# CircuitoClasificadorv1.net
KiCad netlist of a schematic drawn in EAGLE
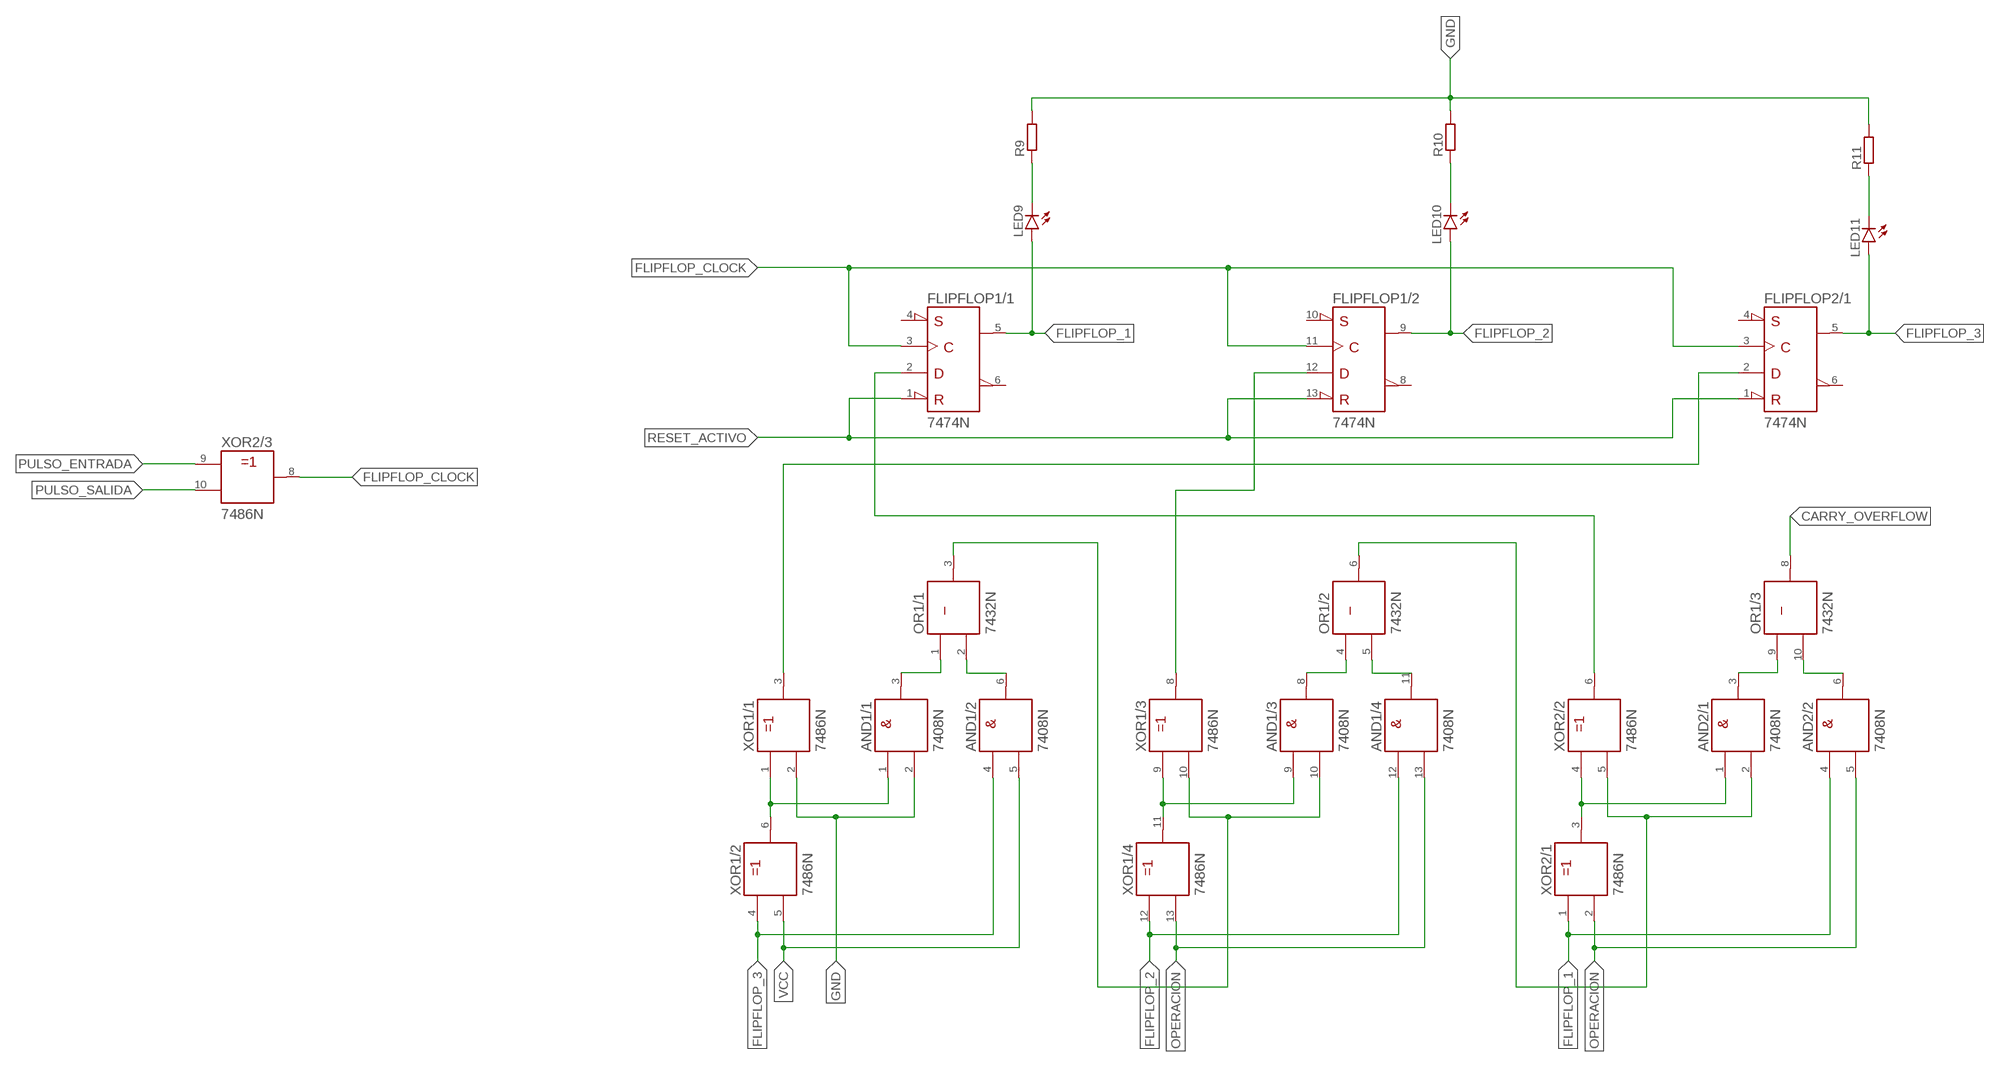
[diagram p0: schematic, sheet 1, part 1 of 2]
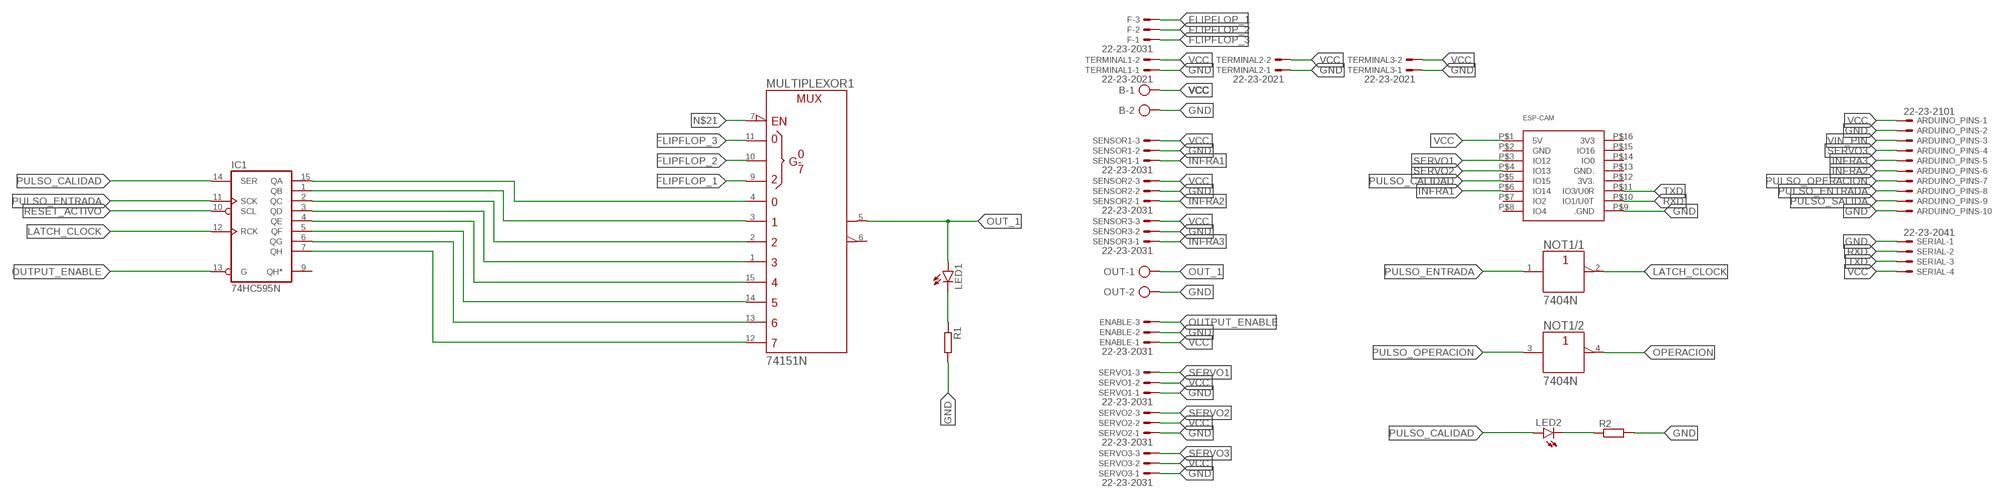
[diagram p1: schematic, sheet 1, part 2 of 2]

(export (version "E")
  (design (tool "Eeschema 10.0.6"))
  (components
    (comp (ref "AND1")
      (value "7408N")
      (footprint "eagle-import:DIL14")
      (libsource (lib "eagle-import") (part "7408N"))
    )
    (comp (ref "AND2")
      (value "7408N")
      (footprint "eagle-import:DIL14")
      (libsource (lib "eagle-import") (part "7408N"))
    )
    (comp (ref "ARDUINO_PINS")
      (value "22-23-2101")
      (footprint "eagle-import:22-23-2101")
      (fields (field (name "MF") "MOLEX"))
      (libsource (lib "eagle-import") (part "22-23-2101"))
    )
    (comp (ref "B")
      (value "AK500/2")
      (footprint "eagle-import:AK500_2")
      (libsource (lib "eagle-import") (part "AK500/2"))
    )
    (comp (ref "ENABLE")
      (value "22-23-2031")
      (footprint "eagle-import:22-23-2031")
      (fields (field (name "MF") "MOLEX"))
      (libsource (lib "eagle-import") (part "22-23-2031"))
    )
    (comp (ref "ESP-CAM")
      (value "ESP32-CAM")
      (footprint "eagle-import:ESP32-CAM")
      (fields (field (name "MF") "AI-Thinker"))
      (libsource (lib "eagle-import") (part "ESP32-CAM"))
    )
    (comp (ref "F")
      (value "22-23-2031")
      (footprint "eagle-import:22-23-2031")
      (fields (field (name "MF") "MOLEX"))
      (libsource (lib "eagle-import") (part "22-23-2031"))
    )
    (comp (ref "FLIPFLOP1")
      (value "7474N")
      (footprint "eagle-import:DIL14")
      (libsource (lib "eagle-import") (part "7474N"))
    )
    (comp (ref "FLIPFLOP2")
      (value "7474N")
      (footprint "eagle-import:DIL14")
      (libsource (lib "eagle-import") (part "7474N"))
    )
    (comp (ref "IC1")
      (value "74HC595N")
      (footprint "eagle-import:DIL16")
      (libsource (lib "eagle-import") (part "74595NHC"))
    )
    (comp (ref "LED1")
      (value "LED5MM")
      (footprint "eagle-import:LED5MM")
      (libsource (lib "eagle-import") (part "LED5MM"))
    )
    (comp (ref "LED2")
      (value "LED5MM")
      (footprint "eagle-import:LED5MM")
      (libsource (lib "eagle-import") (part "LED5MM"))
    )
    (comp (ref "LED9")
      (value "LED5MM")
      (footprint "eagle-import:LED5MM")
      (libsource (lib "eagle-import") (part "LED5MM"))
    )
    (comp (ref "LED10")
      (value "LED5MM")
      (footprint "eagle-import:LED5MM")
      (libsource (lib "eagle-import") (part "LED5MM"))
    )
    (comp (ref "LED11")
      (value "LED5MM")
      (footprint "eagle-import:LED5MM")
      (libsource (lib "eagle-import") (part "LED5MM"))
    )
    (comp (ref "MULTIPLEXOR1")
      (value "74151N")
      (footprint "eagle-import:DIL16")
      (libsource (lib "eagle-import") (part "74151N"))
    )
    (comp (ref "NOT1")
      (value "7404N")
      (footprint "eagle-import:DIL14")
      (libsource (lib "eagle-import") (part "7404N"))
    )
    (comp (ref "OR1")
      (value "7432N")
      (footprint "eagle-import:DIL14")
      (libsource (lib "eagle-import") (part "7432N"))
    )
    (comp (ref "OUT")
      (value "AK500/2-H")
      (footprint "eagle-import:AK500_2-H")
      (libsource (lib "eagle-import") (part "AK500/2-H"))
    )
    (comp (ref "R1")
      (value "R-EU_0207/10")
      (footprint "eagle-import:0207_10")
      (libsource (lib "eagle-import") (part "R-EU_0207/10"))
    )
    (comp (ref "R2")
      (value "R-EU_0207/10")
      (footprint "eagle-import:0207_10")
      (libsource (lib "eagle-import") (part "R-EU_0207/10"))
    )
    (comp (ref "R9")
      (value "R-EU_0207/10")
      (footprint "eagle-import:0207_10")
      (libsource (lib "eagle-import") (part "R-EU_0207/10"))
    )
    (comp (ref "R10")
      (value "R-EU_0207/10")
      (footprint "eagle-import:0207_10")
      (libsource (lib "eagle-import") (part "R-EU_0207/10"))
    )
    (comp (ref "R11")
      (value "R-EU_0207/10")
      (footprint "eagle-import:0207_10")
      (libsource (lib "eagle-import") (part "R-EU_0207/10"))
    )
    (comp (ref "SENSOR1")
      (value "22-23-2031")
      (footprint "eagle-import:22-23-2031")
      (fields (field (name "MF") "MOLEX"))
      (libsource (lib "eagle-import") (part "22-23-2031"))
    )
    (comp (ref "SENSOR2")
      (value "22-23-2031")
      (footprint "eagle-import:22-23-2031")
      (fields (field (name "MF") "MOLEX"))
      (libsource (lib "eagle-import") (part "22-23-2031"))
    )
    (comp (ref "SENSOR3")
      (value "22-23-2031")
      (footprint "eagle-import:22-23-2031")
      (fields (field (name "MF") "MOLEX"))
      (libsource (lib "eagle-import") (part "22-23-2031"))
    )
    (comp (ref "SERIAL")
      (value "22-23-2041")
      (footprint "eagle-import:22-23-2041")
      (fields (field (name "MF") "MOLEX"))
      (libsource (lib "eagle-import") (part "22-23-2041"))
    )
    (comp (ref "SERVO1")
      (value "22-23-2031")
      (footprint "eagle-import:22-23-2031")
      (fields (field (name "MF") "MOLEX"))
      (libsource (lib "eagle-import") (part "22-23-2031"))
    )
    (comp (ref "SERVO2")
      (value "22-23-2031")
      (footprint "eagle-import:22-23-2031")
      (fields (field (name "MF") "MOLEX"))
      (libsource (lib "eagle-import") (part "22-23-2031"))
    )
    (comp (ref "SERVO3")
      (value "22-23-2031")
      (footprint "eagle-import:22-23-2031")
      (fields (field (name "MF") "MOLEX"))
      (libsource (lib "eagle-import") (part "22-23-2031"))
    )
    (comp (ref "TERMINAL1")
      (value "22-23-2021")
      (footprint "eagle-import:22-23-2021")
      (fields (field (name "MF") "MOLEX"))
      (libsource (lib "eagle-import") (part "22-23-2021"))
    )
    (comp (ref "TERMINAL2")
      (value "22-23-2021")
      (footprint "eagle-import:22-23-2021")
      (fields (field (name "MF") "MOLEX"))
      (libsource (lib "eagle-import") (part "22-23-2021"))
    )
    (comp (ref "TERMINAL3")
      (value "22-23-2021")
      (footprint "eagle-import:22-23-2021")
      (fields (field (name "MF") "MOLEX"))
      (libsource (lib "eagle-import") (part "22-23-2021"))
    )
    (comp (ref "XOR1")
      (value "7486N")
      (footprint "eagle-import:DIL14")
      (libsource (lib "eagle-import") (part "7486N"))
    )
    (comp (ref "XOR2")
      (value "7486N")
      (footprint "eagle-import:DIL14")
      (libsource (lib "eagle-import") (part "7486N"))
    )
  )
  (nets
    (net (code "1") (name "CARRY_OVERFLOW") (class "Default")
      (node (ref "OR1") (pin "8") (pinfunction "Y_8") (pintype "output"))
    )
    (net (code "2") (name "FLIPFLOP_1") (class "Default")
      (node (ref "AND2") (pin "4") (pinfunction "A_4") (pintype "input"))
      (node (ref "F") (pin "3") (pinfunction "S_3") (pintype "passive"))
      (node (ref "FLIPFLOP1") (pin "5") (pinfunction "Q_5") (pintype "output"))
      (node (ref "LED9") (pin "A") (pinfunction "A_A") (pintype "passive"))
      (node (ref "MULTIPLEXOR1") (pin "9") (pinfunction "C_9") (pintype "input"))
      (node (ref "XOR2") (pin "1") (pinfunction "A_1") (pintype "input"))
    )
    (net (code "3") (name "FLIPFLOP_2") (class "Default")
      (node (ref "AND1") (pin "12") (pinfunction "A_12") (pintype "input"))
      (node (ref "F") (pin "2") (pinfunction "S_2") (pintype "passive"))
      (node (ref "FLIPFLOP1") (pin "9") (pinfunction "Q_9") (pintype "output"))
      (node (ref "LED10") (pin "A") (pinfunction "A_A") (pintype "passive"))
      (node (ref "MULTIPLEXOR1") (pin "10") (pinfunction "B_10") (pintype "input"))
      (node (ref "XOR1") (pin "12") (pinfunction "A_12") (pintype "input"))
    )
    (net (code "4") (name "FLIPFLOP_3") (class "Default")
      (node (ref "AND1") (pin "4") (pinfunction "A_4") (pintype "input"))
      (node (ref "F") (pin "1") (pinfunction "S_1") (pintype "passive"))
      (node (ref "FLIPFLOP2") (pin "5") (pinfunction "Q_5") (pintype "output"))
      (node (ref "LED11") (pin "A") (pinfunction "A_A") (pintype "passive"))
      (node (ref "MULTIPLEXOR1") (pin "11") (pinfunction "A_11") (pintype "input"))
      (node (ref "XOR1") (pin "4") (pinfunction "A_4") (pintype "input"))
    )
    (net (code "5") (name "FLIPFLOP_CLOCK") (class "Default")
      (node (ref "FLIPFLOP1") (pin "11") (pinfunction "CLK_11") (pintype "input"))
      (node (ref "FLIPFLOP1") (pin "3") (pinfunction "CLK_3") (pintype "input"))
      (node (ref "FLIPFLOP2") (pin "3") (pinfunction "CLK_3") (pintype "input"))
      (node (ref "XOR2") (pin "8") (pinfunction "Y_8") (pintype "output"))
    )
    (net (code "6") (name "GND") (class "Default")
      (node (ref "AND1") (pin "2") (pinfunction "B_2") (pintype "input"))
      (node (ref "ARDUINO_PINS") (pin "10") (pinfunction "S_10") (pintype "passive"))
      (node (ref "ARDUINO_PINS") (pin "2") (pinfunction "S_2") (pintype "passive"))
      (node (ref "B") (pin "2") (pinfunction "KL_2") (pintype "passive"))
      (node (ref "ENABLE") (pin "2") (pinfunction "S_2") (pintype "passive"))
      (node (ref "ESP-CAM") (pin "P$9") (pinfunction ".GND_P$9") (pintype "bidirectional"))
      (node (ref "OUT") (pin "2") (pinfunction "KL_2") (pintype "passive"))
      (node (ref "R1") (pin "2") (pinfunction "2_2") (pintype "passive"))
      (node (ref "R10") (pin "2") (pinfunction "2_2") (pintype "passive"))
      (node (ref "R11") (pin "2") (pinfunction "2_2") (pintype "passive"))
      (node (ref "R2") (pin "2") (pinfunction "2_2") (pintype "passive"))
      (node (ref "R9") (pin "2") (pinfunction "2_2") (pintype "passive"))
      (node (ref "SENSOR1") (pin "2") (pinfunction "S_2") (pintype "passive"))
      (node (ref "SENSOR2") (pin "2") (pinfunction "S_2") (pintype "passive"))
      (node (ref "SENSOR3") (pin "2") (pinfunction "S_2") (pintype "passive"))
      (node (ref "SERIAL") (pin "1") (pinfunction "S_1") (pintype "passive"))
      (node (ref "SERVO1") (pin "1") (pinfunction "S_1") (pintype "passive"))
      (node (ref "SERVO2") (pin "1") (pinfunction "S_1") (pintype "passive"))
      (node (ref "SERVO3") (pin "1") (pinfunction "S_1") (pintype "passive"))
      (node (ref "TERMINAL1") (pin "1") (pinfunction "S_1") (pintype "passive"))
      (node (ref "TERMINAL2") (pin "1") (pinfunction "S_1") (pintype "passive"))
      (node (ref "TERMINAL3") (pin "1") (pinfunction "S_1") (pintype "passive"))
      (node (ref "XOR1") (pin "2") (pinfunction "B_2") (pintype "input"))
    )
    (net (code "7") (name "INFRA1") (class "Default")
      (node (ref "ESP-CAM") (pin "P$6") (pinfunction "IO14_P$6") (pintype "bidirectional"))
      (node (ref "SENSOR1") (pin "1") (pinfunction "S_1") (pintype "passive"))
    )
    (net (code "8") (name "INFRA2") (class "Default")
      (node (ref "ARDUINO_PINS") (pin "6") (pinfunction "S_6") (pintype "passive"))
      (node (ref "SENSOR2") (pin "1") (pinfunction "S_1") (pintype "passive"))
    )
    (net (code "9") (name "INFRA3") (class "Default")
      (node (ref "ARDUINO_PINS") (pin "5") (pinfunction "S_5") (pintype "passive"))
      (node (ref "SENSOR3") (pin "1") (pinfunction "S_1") (pintype "passive"))
    )
    (net (code "10") (name "LATCH_CLOCK") (class "Default")
      (node (ref "IC1") (pin "12") (pinfunction "RCK_12") (pintype "input"))
      (node (ref "NOT1") (pin "2") (pinfunction "Y_2") (pintype "output"))
    )
    (net (code "11") (name "N$21") (class "Default")
      (node (ref "MULTIPLEXOR1") (pin "7") (pinfunction "~{G}_7") (pintype "input"))
    )
    (net (code "12") (name "Net-(AND1C-A)") (class "Default")
      (node (ref "AND1") (pin "1") (pinfunction "A_1") (pintype "input"))
      (node (ref "XOR1") (pin "1") (pinfunction "A_1") (pintype "input"))
      (node (ref "XOR1") (pin "6") (pinfunction "Y_6") (pintype "output"))
    )
    (net (code "13") (name "Net-(AND1C-Y)") (class "Default")
      (node (ref "AND1") (pin "3") (pinfunction "Y_3") (pintype "output"))
      (node (ref "OR1") (pin "1") (pinfunction "A_1") (pintype "input"))
    )
    (net (code "14") (name "Net-(AND1D-Y)") (class "Default")
      (node (ref "AND1") (pin "6") (pinfunction "Y_6") (pintype "output"))
      (node (ref "OR1") (pin "2") (pinfunction "B_2") (pintype "input"))
    )
    (net (code "15") (name "Net-(AND1E-A)") (class "Default")
      (node (ref "AND1") (pin "9") (pinfunction "A_9") (pintype "input"))
      (node (ref "XOR1") (pin "11") (pinfunction "Y_11") (pintype "output"))
      (node (ref "XOR1") (pin "9") (pinfunction "A_9") (pintype "input"))
    )
    (net (code "16") (name "Net-(AND1E-B)") (class "Default")
      (node (ref "AND1") (pin "10") (pinfunction "B_10") (pintype "input"))
      (node (ref "OR1") (pin "3") (pinfunction "Y_3") (pintype "output"))
      (node (ref "XOR1") (pin "10") (pinfunction "B_10") (pintype "input"))
    )
    (net (code "17") (name "Net-(AND1E-Y)") (class "Default")
      (node (ref "AND1") (pin "8") (pinfunction "Y_8") (pintype "output"))
      (node (ref "OR1") (pin "4") (pinfunction "A_4") (pintype "input"))
    )
    (net (code "18") (name "Net-(AND1F-Y)") (class "Default")
      (node (ref "AND1") (pin "11") (pinfunction "Y_11") (pintype "output"))
      (node (ref "OR1") (pin "5") (pinfunction "B_5") (pintype "input"))
    )
    (net (code "19") (name "Net-(AND2C-A)") (class "Default")
      (node (ref "AND2") (pin "1") (pinfunction "A_1") (pintype "input"))
      (node (ref "XOR2") (pin "3") (pinfunction "Y_3") (pintype "output"))
      (node (ref "XOR2") (pin "4") (pinfunction "A_4") (pintype "input"))
    )
    (net (code "20") (name "Net-(AND2C-B)") (class "Default")
      (node (ref "AND2") (pin "2") (pinfunction "B_2") (pintype "input"))
      (node (ref "OR1") (pin "6") (pinfunction "Y_6") (pintype "output"))
      (node (ref "XOR2") (pin "5") (pinfunction "B_5") (pintype "input"))
    )
    (net (code "21") (name "Net-(AND2C-Y)") (class "Default")
      (node (ref "AND2") (pin "3") (pinfunction "Y_3") (pintype "output"))
      (node (ref "OR1") (pin "9") (pinfunction "A_9") (pintype "input"))
    )
    (net (code "22") (name "Net-(AND2D-Y)") (class "Default")
      (node (ref "AND2") (pin "6") (pinfunction "Y_6") (pintype "output"))
      (node (ref "OR1") (pin "10") (pinfunction "B_10") (pintype "input"))
    )
    (net (code "23") (name "Net-(FLIPFLOP1C-D)") (class "Default")
      (node (ref "FLIPFLOP1") (pin "2") (pinfunction "D_2") (pintype "input"))
      (node (ref "XOR2") (pin "6") (pinfunction "Y_6") (pintype "output"))
    )
    (net (code "24") (name "Net-(FLIPFLOP1D-D)") (class "Default")
      (node (ref "FLIPFLOP1") (pin "12") (pinfunction "D_12") (pintype "input"))
      (node (ref "XOR1") (pin "8") (pinfunction "Y_8") (pintype "output"))
    )
    (net (code "25") (name "Net-(FLIPFLOP2C-D)") (class "Default")
      (node (ref "FLIPFLOP2") (pin "2") (pinfunction "D_2") (pintype "input"))
      (node (ref "XOR1") (pin "3") (pinfunction "Y_3") (pintype "output"))
    )
    (net (code "26") (name "Net-(IC1A-QA)") (class "Default")
      (node (ref "IC1") (pin "15") (pinfunction "QA_15") (pintype "tri_state"))
      (node (ref "MULTIPLEXOR1") (pin "4") (pinfunction "D0_4") (pintype "input"))
    )
    (net (code "27") (name "Net-(IC1A-QB)") (class "Default")
      (node (ref "IC1") (pin "1") (pinfunction "QB_1") (pintype "tri_state"))
      (node (ref "MULTIPLEXOR1") (pin "3") (pinfunction "D1_3") (pintype "input"))
    )
    (net (code "28") (name "Net-(IC1A-QC)") (class "Default")
      (node (ref "IC1") (pin "2") (pinfunction "QC_2") (pintype "tri_state"))
      (node (ref "MULTIPLEXOR1") (pin "2") (pinfunction "D2_2") (pintype "input"))
    )
    (net (code "29") (name "Net-(IC1A-QD)") (class "Default")
      (node (ref "IC1") (pin "3") (pinfunction "QD_3") (pintype "tri_state"))
      (node (ref "MULTIPLEXOR1") (pin "1") (pinfunction "D3_1") (pintype "input"))
    )
    (net (code "30") (name "Net-(IC1A-QE)") (class "Default")
      (node (ref "IC1") (pin "4") (pinfunction "QE_4") (pintype "tri_state"))
      (node (ref "MULTIPLEXOR1") (pin "15") (pinfunction "D4_15") (pintype "input"))
    )
    (net (code "31") (name "Net-(IC1A-QF)") (class "Default")
      (node (ref "IC1") (pin "5") (pinfunction "QF_5") (pintype "tri_state"))
      (node (ref "MULTIPLEXOR1") (pin "14") (pinfunction "D5_14") (pintype "input"))
    )
    (net (code "32") (name "Net-(IC1A-QG)") (class "Default")
      (node (ref "IC1") (pin "6") (pinfunction "QG_6") (pintype "tri_state"))
      (node (ref "MULTIPLEXOR1") (pin "13") (pinfunction "D6_13") (pintype "input"))
    )
    (net (code "33") (name "Net-(IC1A-QH)") (class "Default")
      (node (ref "IC1") (pin "7") (pinfunction "QH_7") (pintype "tri_state"))
      (node (ref "MULTIPLEXOR1") (pin "12") (pinfunction "D7_12") (pintype "input"))
    )
    (net (code "34") (name "Net-(LED1-C)") (class "Default")
      (node (ref "LED1") (pin "K") (pinfunction "C_K") (pintype "passive"))
      (node (ref "R1") (pin "1") (pinfunction "1_1") (pintype "passive"))
    )
    (net (code "35") (name "Net-(LED2-C)") (class "Default")
      (node (ref "LED2") (pin "K") (pinfunction "C_K") (pintype "passive"))
      (node (ref "R2") (pin "1") (pinfunction "1_1") (pintype "passive"))
    )
    (net (code "36") (name "Net-(LED9-C)") (class "Default")
      (node (ref "LED9") (pin "K") (pinfunction "C_K") (pintype "passive"))
      (node (ref "R9") (pin "1") (pinfunction "1_1") (pintype "passive"))
    )
    (net (code "37") (name "Net-(LED10-C)") (class "Default")
      (node (ref "LED10") (pin "K") (pinfunction "C_K") (pintype "passive"))
      (node (ref "R10") (pin "1") (pinfunction "1_1") (pintype "passive"))
    )
    (net (code "38") (name "Net-(LED11-C)") (class "Default")
      (node (ref "LED11") (pin "K") (pinfunction "C_K") (pintype "passive"))
      (node (ref "R11") (pin "1") (pinfunction "1_1") (pintype "passive"))
    )
    (net (code "39") (name "OPERACION") (class "Default")
      (node (ref "AND1") (pin "13") (pinfunction "B_13") (pintype "input"))
      (node (ref "AND2") (pin "5") (pinfunction "B_5") (pintype "input"))
      (node (ref "NOT1") (pin "4") (pinfunction "Y_4") (pintype "output"))
      (node (ref "XOR1") (pin "13") (pinfunction "B_13") (pintype "input"))
      (node (ref "XOR2") (pin "2") (pinfunction "B_2") (pintype "input"))
    )
    (net (code "40") (name "OUTPUT_ENABLE") (class "Default")
      (node (ref "ENABLE") (pin "3") (pinfunction "S_3") (pintype "passive"))
      (node (ref "IC1") (pin "13") (pinfunction "G_13") (pintype "input"))
    )
    (net (code "41") (name "OUT_1") (class "Default")
      (node (ref "LED1") (pin "A") (pinfunction "A_A") (pintype "passive"))
      (node (ref "MULTIPLEXOR1") (pin "5") (pinfunction "Y_5") (pintype "output"))
      (node (ref "OUT") (pin "1") (pinfunction "KL_1") (pintype "passive"))
    )
    (net (code "42") (name "PULSO_CALIDAD") (class "Default")
      (node (ref "ESP-CAM") (pin "P$5") (pinfunction "IO15_P$5") (pintype "bidirectional"))
      (node (ref "IC1") (pin "14") (pinfunction "SER_14") (pintype "input"))
      (node (ref "LED2") (pin "A") (pinfunction "A_A") (pintype "passive"))
    )
    (net (code "43") (name "PULSO_ENTRADA") (class "Default")
      (node (ref "ARDUINO_PINS") (pin "8") (pinfunction "S_8") (pintype "passive"))
      (node (ref "IC1") (pin "11") (pinfunction "SCK_11") (pintype "input"))
      (node (ref "NOT1") (pin "1") (pinfunction "A_1") (pintype "input"))
      (node (ref "XOR2") (pin "9") (pinfunction "A_9") (pintype "input"))
    )
    (net (code "44") (name "PULSO_OPERACION") (class "Default")
      (node (ref "ARDUINO_PINS") (pin "7") (pinfunction "S_7") (pintype "passive"))
      (node (ref "NOT1") (pin "3") (pinfunction "A_3") (pintype "input"))
    )
    (net (code "45") (name "PULSO_SALIDA") (class "Default")
      (node (ref "ARDUINO_PINS") (pin "9") (pinfunction "S_9") (pintype "passive"))
      (node (ref "XOR2") (pin "10") (pinfunction "B_10") (pintype "input"))
    )
    (net (code "46") (name "RESET_ACTIVO") (class "Default")
      (node (ref "FLIPFLOP1") (pin "1") (pinfunction "~{CLR}_1") (pintype "input"))
      (node (ref "FLIPFLOP1") (pin "13") (pinfunction "~{CLR}_13") (pintype "input"))
      (node (ref "FLIPFLOP2") (pin "1") (pinfunction "~{CLR}_1") (pintype "input"))
      (node (ref "IC1") (pin "10") (pinfunction "SCL_10") (pintype "input"))
    )
    (net (code "47") (name "RXD") (class "Default")
      (node (ref "ESP-CAM") (pin "P$10") (pinfunction "IO1/U0T_P$10") (pintype "bidirectional"))
      (node (ref "SERIAL") (pin "2") (pinfunction "S_2") (pintype "passive"))
    )
    (net (code "48") (name "SERVO1") (class "Default")
      (node (ref "ESP-CAM") (pin "P$3") (pinfunction "IO12_P$3") (pintype "bidirectional"))
      (node (ref "SERVO1") (pin "3") (pinfunction "S_3") (pintype "passive"))
    )
    (net (code "49") (name "SERVO2") (class "Default")
      (node (ref "ESP-CAM") (pin "P$4") (pinfunction "IO13_P$4") (pintype "bidirectional"))
      (node (ref "SERVO2") (pin "3") (pinfunction "S_3") (pintype "passive"))
    )
    (net (code "50") (name "SERVO3") (class "Default")
      (node (ref "ARDUINO_PINS") (pin "4") (pinfunction "S_4") (pintype "passive"))
      (node (ref "SERVO3") (pin "3") (pinfunction "S_3") (pintype "passive"))
    )
    (net (code "51") (name "TXD") (class "Default")
      (node (ref "ESP-CAM") (pin "P$11") (pinfunction "IO3/U0R_P$11") (pintype "bidirectional"))
      (node (ref "SERIAL") (pin "3") (pinfunction "S_3") (pintype "passive"))
    )
    (net (code "52") (name "VCC") (class "Default")
      (node (ref "AND1") (pin "5") (pinfunction "B_5") (pintype "input"))
      (node (ref "ARDUINO_PINS") (pin "1") (pinfunction "S_1") (pintype "passive"))
      (node (ref "B") (pin "1") (pinfunction "KL_1") (pintype "passive"))
      (node (ref "ENABLE") (pin "1") (pinfunction "S_1") (pintype "passive"))
      (node (ref "ESP-CAM") (pin "P$1") (pinfunction "5V_P$1") (pintype "bidirectional"))
      (node (ref "SENSOR1") (pin "3") (pinfunction "S_3") (pintype "passive"))
      (node (ref "SENSOR2") (pin "3") (pinfunction "S_3") (pintype "passive"))
      (node (ref "SENSOR3") (pin "3") (pinfunction "S_3") (pintype "passive"))
      (node (ref "SERIAL") (pin "4") (pinfunction "S_4") (pintype "passive"))
      (node (ref "SERVO1") (pin "2") (pinfunction "S_2") (pintype "passive"))
      (node (ref "SERVO2") (pin "2") (pinfunction "S_2") (pintype "passive"))
      (node (ref "SERVO3") (pin "2") (pinfunction "S_2") (pintype "passive"))
      (node (ref "TERMINAL1") (pin "2") (pinfunction "S_2") (pintype "passive"))
      (node (ref "TERMINAL2") (pin "2") (pinfunction "S_2") (pintype "passive"))
      (node (ref "TERMINAL3") (pin "2") (pinfunction "S_2") (pintype "passive"))
      (node (ref "XOR1") (pin "5") (pinfunction "B_5") (pintype "input"))
    )
    (net (code "53") (name "VIN_PIN") (class "Default")
      (node (ref "ARDUINO_PINS") (pin "3") (pinfunction "S_3") (pintype "passive"))
    )
    (net (code "54") (name "unconnected-(ESP-CAM-3V3-PadP$16)") (class "Default")
      (node (ref "ESP-CAM") (pin "P$16") (pinfunction "3V3_P$16") (pintype "bidirectional"))
    )
    (net (code "55") (name "unconnected-(ESP-CAM-3V3.-PadP$12)") (class "Default")
      (node (ref "ESP-CAM") (pin "P$12") (pinfunction "3V3._P$12") (pintype "bidirectional"))
    )
    (net (code "56") (name "unconnected-(ESP-CAM-GND-PadP$2)") (class "Default")
      (node (ref "ESP-CAM") (pin "P$2") (pinfunction "GND_P$2") (pintype "bidirectional"))
    )
    (net (code "57") (name "unconnected-(ESP-CAM-GND.-PadP$13)") (class "Default")
      (node (ref "ESP-CAM") (pin "P$13") (pinfunction "GND._P$13") (pintype "bidirectional"))
    )
    (net (code "58") (name "unconnected-(ESP-CAM-IO0-PadP$14)") (class "Default")
      (node (ref "ESP-CAM") (pin "P$14") (pinfunction "IO0_P$14") (pintype "bidirectional"))
    )
    (net (code "59") (name "unconnected-(ESP-CAM-IO2-PadP$7)") (class "Default")
      (node (ref "ESP-CAM") (pin "P$7") (pinfunction "IO2_P$7") (pintype "bidirectional"))
    )
    (net (code "60") (name "unconnected-(ESP-CAM-IO4-PadP$8)") (class "Default")
      (node (ref "ESP-CAM") (pin "P$8") (pinfunction "IO4_P$8") (pintype "bidirectional"))
    )
    (net (code "61") (name "unconnected-(ESP-CAM-IO16-PadP$15)") (class "Default")
      (node (ref "ESP-CAM") (pin "P$15") (pinfunction "IO16_P$15") (pintype "bidirectional"))
    )
    (net (code "62") (name "unconnected-(FLIPFLOP1C-~{PRE}-Pad4)") (class "Default")
      (node (ref "FLIPFLOP1") (pin "4") (pinfunction "~{PRE}_4") (pintype "input"))
    )
    (net (code "63") (name "unconnected-(FLIPFLOP1C-~{Q}-Pad6)") (class "Default")
      (node (ref "FLIPFLOP1") (pin "6") (pinfunction "~{Q}_6") (pintype "output"))
    )
    (net (code "64") (name "unconnected-(FLIPFLOP1D-~{PRE}-Pad10)") (class "Default")
      (node (ref "FLIPFLOP1") (pin "10") (pinfunction "~{PRE}_10") (pintype "input"))
    )
    (net (code "65") (name "unconnected-(FLIPFLOP1D-~{Q}-Pad8)") (class "Default")
      (node (ref "FLIPFLOP1") (pin "8") (pinfunction "~{Q}_8") (pintype "output"))
    )
    (net (code "66") (name "unconnected-(FLIPFLOP2C-~{PRE}-Pad4)") (class "Default")
      (node (ref "FLIPFLOP2") (pin "4") (pinfunction "~{PRE}_4") (pintype "input"))
    )
    (net (code "67") (name "unconnected-(FLIPFLOP2C-~{Q}-Pad6)") (class "Default")
      (node (ref "FLIPFLOP2") (pin "6") (pinfunction "~{Q}_6") (pintype "output"))
    )
    (net (code "68") (name "unconnected-(IC1A-QH*-Pad9)") (class "Default")
      (node (ref "IC1") (pin "9") (pinfunction "QH*_9") (pintype "tri_state"))
    )
    (net (code "69") (name "unconnected-(MULTIPLEXOR1C-W-Pad6)") (class "Default")
      (node (ref "MULTIPLEXOR1") (pin "6") (pinfunction "W_6") (pintype "output"))
    )
  )
)
